# GENERADORA_V1_5.net
KiCad netlist of a schematic drawn in Altium Designer
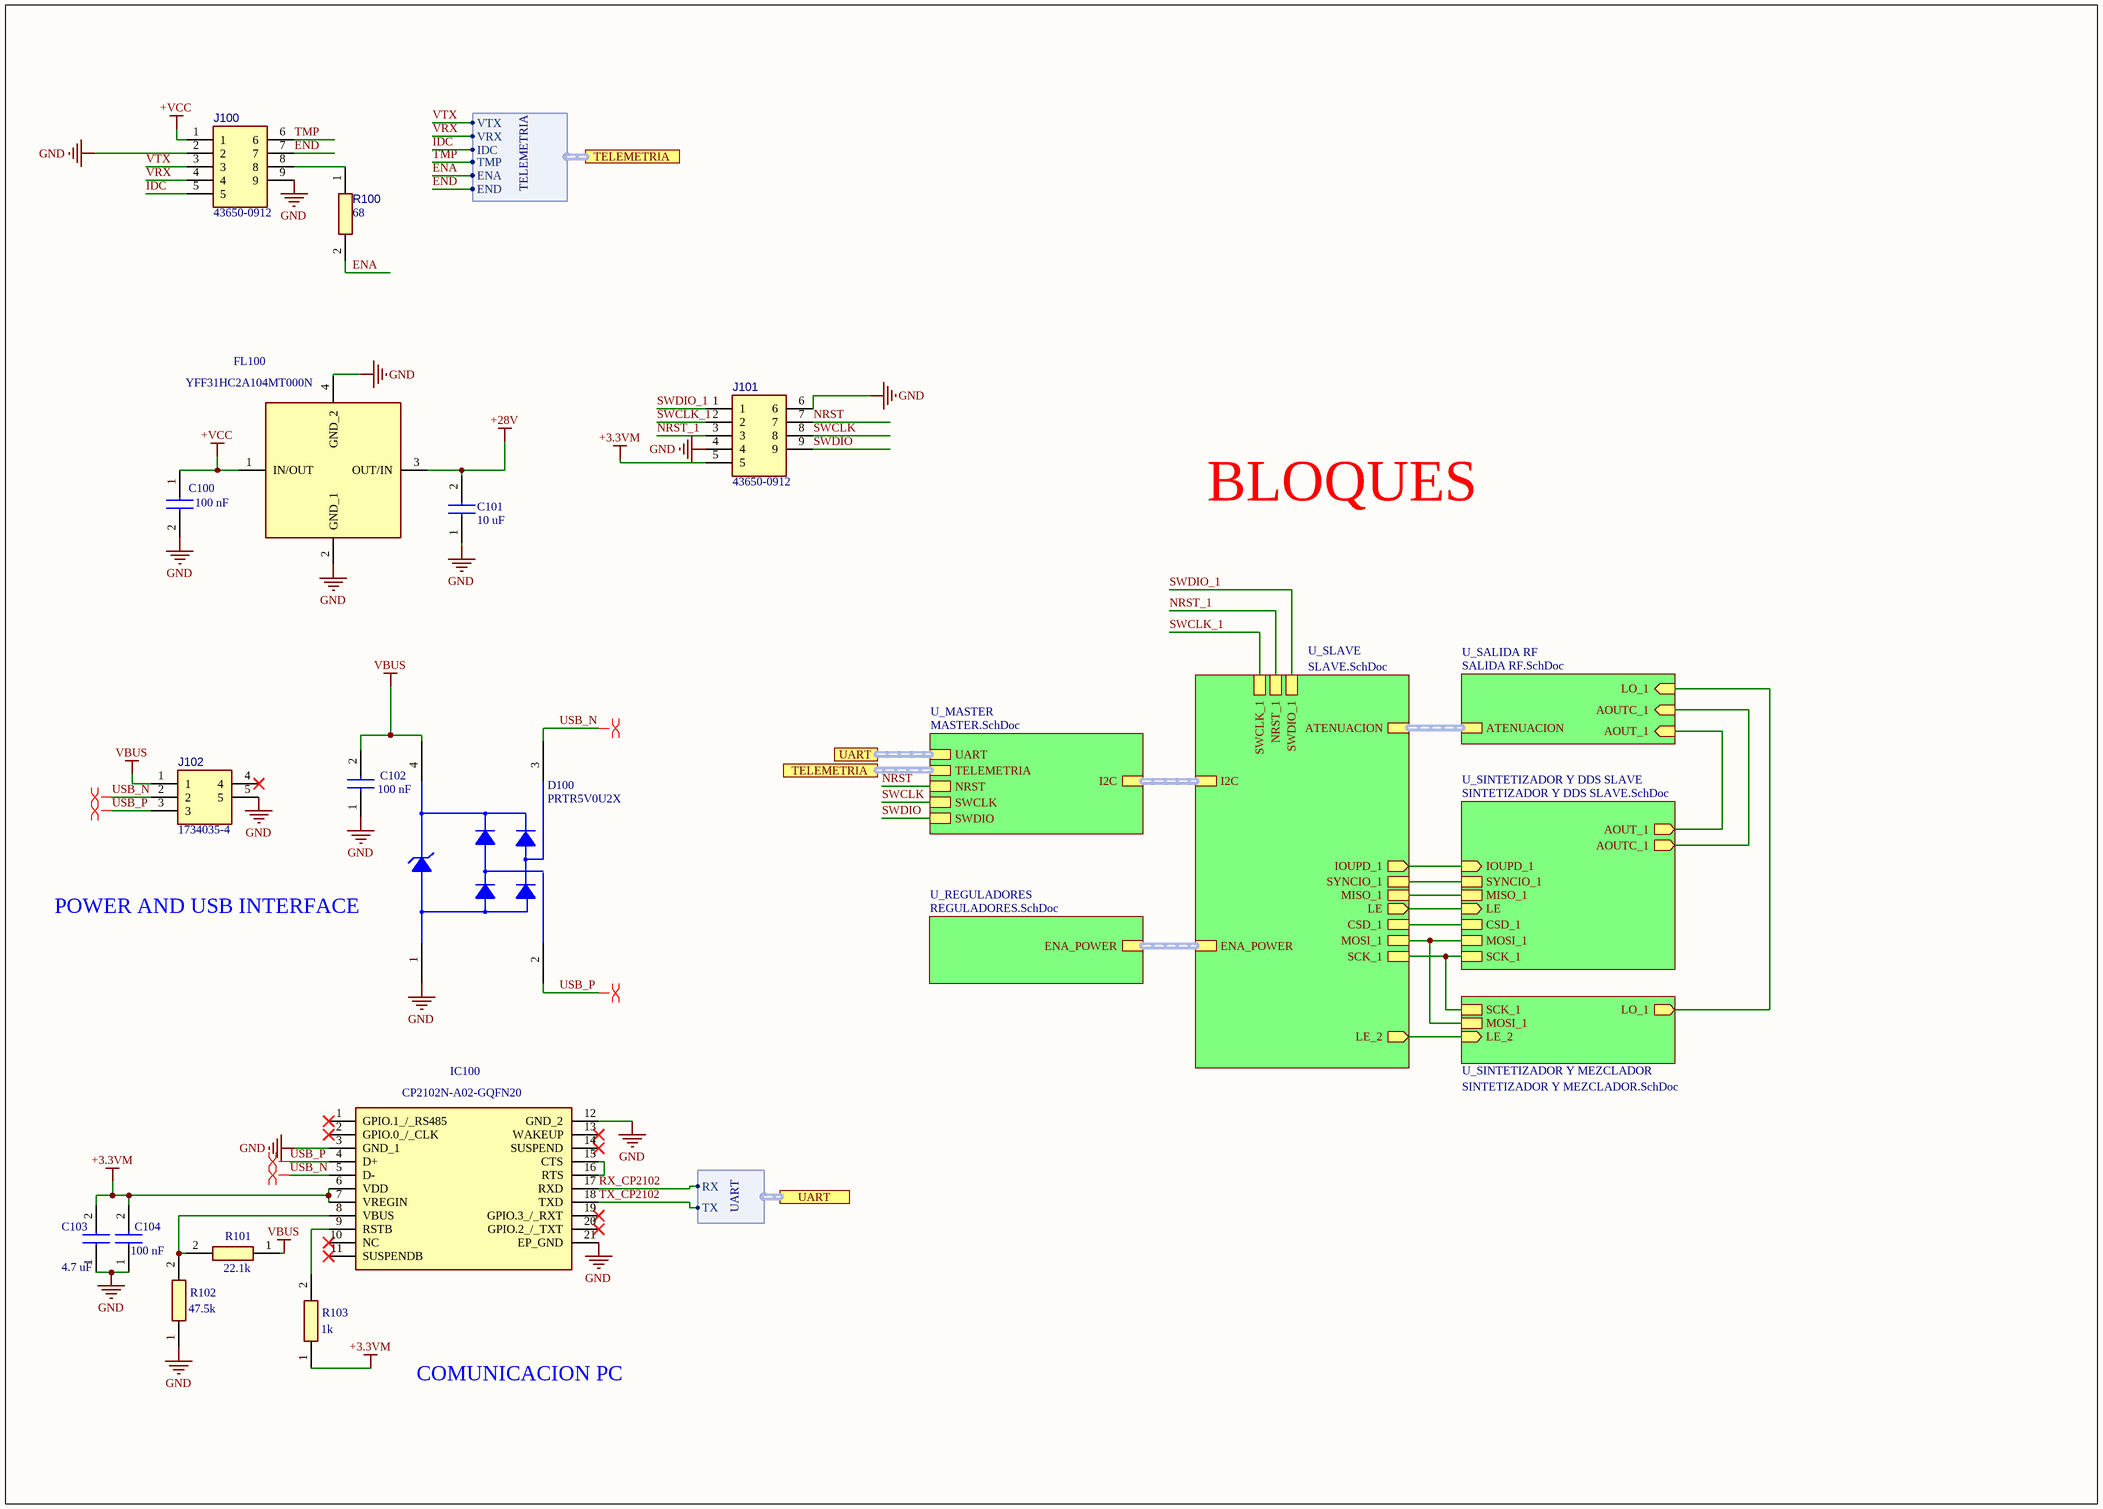
[diagram p0: GENERADORA V1.5.SchDoc]

(export (version "E")
  (design (tool "Eeschema 10.0.6"))
  (components
    (comp (ref "C100")
      (value "100 nF")
      (footprint "SamacSys:CAPC3216X94N")
      (description "Capacitor")
      (fields
        (field (name "MANUFACTURER_PART_NUMBER") "KAM31BR81H103KT")
        (field (name "MOUSER PART NUMBER") "581-KAM31BR81H103KT")
      )
      (libsource (lib "LIBRERIA_GEN_V2.0") (part "KAM31BR81H103KT"))
    )
    (comp (ref "C101")
      (value "10 uF")
      (footprint "SamacSys:CAPC3216X94N")
      (description "Capacitor")
      (fields
        (field (name "MANUFACTURER_PART_NUMBER") "KAM31BR81H103KT")
        (field (name "MOUSER PART NUMBER") "581-KAM31BR81H103KT")
      )
      (libsource (lib "LIBRERIA_GEN_V2.0") (part "KAM31BR81H103KT"))
    )
    (comp (ref "C102")
      (value "100 nF")
      (footprint "SamacSys:CAPC3216X94N")
      (description "Capacitor")
      (fields
        (field (name "MANUFACTURER_PART_NUMBER") "KAM31BR81H103KT")
        (field (name "MOUSER PART NUMBER") "581-KAM31BR81H103KT")
      )
      (libsource (lib "LIBRERIA_GEN_V2.0") (part "KAM31BR81H103KT"))
    )
    (comp (ref "C103")
      (value "4.7 uF")
      (footprint "SamacSys:C0603")
      (description "Capacitor")
      (fields (field (name "MANUFACTURER_PART_NUMBER") "C0603H470J5GACTU"))
      (libsource (lib "LIBRERIA_GEN_V2.0") (part "C0603H470J5GACTU"))
    )
    (comp (ref "C104")
      (value "100 nF")
      (footprint "SamacSys:C0603")
      (description "Capacitor")
      (fields (field (name "MANUFACTURER_PART_NUMBER") "C0603H470J5GACTU"))
      (libsource (lib "LIBRERIA_GEN_V2.0") (part "C0603H470J5GACTU"))
    )
    (comp (ref "D100")
      (value "PRTR5V0U2X")
      (footprint "AP4-00001")
      (description "Double rail-to-rail USB ESD protection diode")
      (fields (field (name "MANUFACTURER") "Philips"))
      (libsource (lib "SAM4S_Xplained_Pro") (part "PRTR5V0U2X"))
    )
    (comp (ref "FL100")
      (value "YFF31HC2A104MT000N")
      (footprint "SamacSys:YFF31HC2A104MT000N")
      (description "Filter")
      (fields (field (name "MOUSER PART NUMBER") "810-YFF31HC2A104MTHN"))
      (libsource (lib "LIBRERIA_GEN_V2.0") (part "YFF31HC2A104MT000N"))
    )
    (comp (ref "IC100")
      (value "CP2102N-A02-GQFN20")
      (footprint "SamacSys:CP2102NA02GQFN20")
      (description "Integrated Circuit")
      (fields (field (name "MOUSER PART NUMBER") "634-CP2102NA02GQFN20"))
      (libsource (lib "LIBRERIA_GEN_V2.0") (part "CP2102N-A02-GQFN20"))
    )
    (comp (ref "J100")
      (value "43650-0912")
      (footprint "SamacSys:43650-09(12,13,14)")
      (description "Connector")
      (fields (field (name "MOUSER PART NUMBER") "538-43650-0912"))
      (libsource (lib "*") (part "43650-0912"))
    )
    (comp (ref "J101")
      (value "43650-0912")
      (footprint "SamacSys:43650-09(12,13,14)")
      (description "Connector")
      (fields (field (name "MOUSER PART NUMBER") "538-43650-0912"))
      (libsource (lib "*") (part "43650-0912"))
    )
    (comp (ref "J102")
      (value "1734035-4")
      (footprint "SamacSys:1734035-2USB")
      (description "Connector")
      (fields (field (name "MOUSER PART NUMBER") "571-1734035-4"))
      (libsource (lib "SamacSys") (part "1734035-4"))
    )
    (comp (ref "R100")
      (value "68")
      (footprint "SamacSys:RESC1608X55N")
      (description "Resistor")
      (fields
        (field (name "MANUFACTURER_PART_NUMBER") "CR0603-FX-1431ELF")
        (field (name "MOUSER PART NUMBER") "652-CR0603FX-1431ELF")
      )
      (libsource (lib "*") (part "CR0603-FX-1431ELF"))
    )
    (comp (ref "R101")
      (value "22.1k")
      (footprint "SamacSys:RESC1608X55N")
      (description "Resistor")
      (fields
        (field (name "MANUFACTURER_PART_NUMBER") "CR0603-FX-1431ELF")
        (field (name "MOUSER PART NUMBER") "652-CR0603FX-1431ELF")
      )
      (libsource (lib "LIBRERIA_GEN_V2.0") (part "CR0603-FX-1431ELF"))
    )
    (comp (ref "R102")
      (value "47.5k")
      (footprint "SamacSys:RESC1608X55N")
      (description "Resistor")
      (fields
        (field (name "MANUFACTURER_PART_NUMBER") "CR0603-FX-1431ELF")
        (field (name "MOUSER PART NUMBER") "652-CR0603FX-1431ELF")
      )
      (libsource (lib "") (part "CR0603-FX-1431ELF_1"))
    )
    (comp (ref "R103")
      (value "1k")
      (footprint "SamacSys:RESC1608X55N")
      (description "Resistor")
      (fields
        (field (name "MANUFACTURER_PART_NUMBER") "CR0603-FX-1431ELF")
        (field (name "MOUSER PART NUMBER") "652-CR0603FX-1431ELF")
      )
      (libsource (lib "") (part "CR0603-FX-1431ELF_1"))
    )
  )
  (nets
    (net (code "4") (name "+3.3VM") (class "Default")
      (node (ref "C103") (pin "2") (pinfunction "2_2") (pintype "passive"))
      (node (ref "C104") (pin "2") (pinfunction "2_2") (pintype "passive"))
      (node (ref "IC100") (pin "6") (pinfunction "VDD_6") (pintype "passive"))
      (node (ref "IC100") (pin "7") (pinfunction "VREGIN_7") (pintype "passive"))
      (node (ref "J101") (pin "5") (pinfunction "5_5") (pintype "passive"))
      (node (ref "R103") (pin "1") (pinfunction "1_1") (pintype "passive"))
    )
    (net (code "5") (name "+28V") (class "Default")
      (node (ref "C101") (pin "2") (pinfunction "2_2") (pintype "passive"))
      (node (ref "FL100") (pin "3") (pinfunction "OUT/IN_3") (pintype "passive"))
    )
    (net (code "6") (name "+VCC") (class "Default")
      (node (ref "C100") (pin "1") (pinfunction "1_1") (pintype "passive"))
      (node (ref "FL100") (pin "1") (pinfunction "IN/OUT_1") (pintype "passive"))
      (node (ref "J100") (pin "1") (pinfunction "1_1") (pintype "passive"))
    )
    (net (code "11") (name "/ENA") (class "Default")
      (node (ref "R100") (pin "2") (pinfunction "2_2") (pintype "passive"))
    )
    (net (code "13") (name "/END") (class "Default")
      (node (ref "J100") (pin "7") (pinfunction "7_7") (pintype "passive"))
    )
    (net (code "15") (name "/IDC") (class "Default")
      (node (ref "J100") (pin "5") (pinfunction "5_5") (pintype "passive"))
    )
    (net (code "22") (name "/NRST") (class "Default")
      (node (ref "J101") (pin "7") (pinfunction "7_7") (pintype "passive"))
    )
    (net (code "23") (name "/NRST_1") (class "Default")
      (node (ref "J101") (pin "3") (pinfunction "3_3") (pintype "passive"))
    )
    (net (code "24") (name "/RX_CP2102") (class "Default")
      (node (ref "IC100") (pin "17") (pinfunction "RXD_17") (pintype "passive"))
    )
    (net (code "26") (name "/SWCLK") (class "Default")
      (node (ref "J101") (pin "8") (pinfunction "8_8") (pintype "passive"))
    )
    (net (code "27") (name "/SWCLK_1") (class "Default")
      (node (ref "J101") (pin "2") (pinfunction "2_2") (pintype "passive"))
    )
    (net (code "28") (name "/SWDIO") (class "Default")
      (node (ref "J101") (pin "9") (pinfunction "9_9") (pintype "passive"))
    )
    (net (code "29") (name "/SWDIO_1") (class "Default")
      (node (ref "J101") (pin "1") (pinfunction "1_1") (pintype "passive"))
    )
    (net (code "31") (name "/TMP") (class "Default")
      (node (ref "J100") (pin "6") (pinfunction "6_6") (pintype "passive"))
    )
    (net (code "32") (name "/TX_CP2102") (class "Default")
      (node (ref "IC100") (pin "18") (pinfunction "TXD_18") (pintype "passive"))
    )
    (net (code "34") (name "/USB_N") (class "Default")
      (node (ref "D100") (pin "3") (pinfunction "I/O_2_3") (pintype "passive"))
      (node (ref "IC100") (pin "5") (pinfunction "D-_5") (pintype "passive"))
      (node (ref "J102") (pin "2") (pinfunction "2_2") (pintype "passive"))
    )
    (net (code "35") (name "/USB_P") (class "Default")
      (node (ref "D100") (pin "2") (pinfunction "I/O_1_2") (pintype "passive"))
      (node (ref "IC100") (pin "4") (pinfunction "D+_4") (pintype "passive"))
      (node (ref "J102") (pin "3") (pinfunction "3_3") (pintype "passive"))
    )
    (net (code "36") (name "/VRX") (class "Default")
      (node (ref "J100") (pin "4") (pinfunction "4_4") (pintype "passive"))
    )
    (net (code "37") (name "/VTX") (class "Default")
      (node (ref "J100") (pin "3") (pinfunction "3_3") (pintype "passive"))
    )
    (net (code "40") (name "GND") (class "Default")
      (node (ref "C100") (pin "2") (pinfunction "2_2") (pintype "passive"))
      (node (ref "C101") (pin "1") (pinfunction "1_1") (pintype "passive"))
      (node (ref "C102") (pin "1") (pinfunction "1_1") (pintype "passive"))
      (node (ref "C103") (pin "1") (pinfunction "1_1") (pintype "passive"))
      (node (ref "C104") (pin "1") (pinfunction "1_1") (pintype "passive"))
      (node (ref "D100") (pin "1") (pinfunction "GND_1") (pintype "passive"))
      (node (ref "FL100") (pin "2") (pinfunction "GND_1_2") (pintype "passive"))
      (node (ref "FL100") (pin "4") (pinfunction "GND_2_4") (pintype "passive"))
      (node (ref "IC100") (pin "12") (pinfunction "GND_2_12") (pintype "passive"))
      (node (ref "IC100") (pin "21") (pinfunction "EP_GND_21") (pintype "passive"))
      (node (ref "IC100") (pin "3") (pinfunction "GND_1_3") (pintype "passive"))
      (node (ref "J100") (pin "2") (pinfunction "2_2") (pintype "passive"))
      (node (ref "J100") (pin "9") (pinfunction "9_9") (pintype "passive"))
      (node (ref "J101") (pin "4") (pinfunction "4_4") (pintype "passive"))
      (node (ref "J101") (pin "6") (pinfunction "6_6") (pintype "passive"))
      (node (ref "J102") (pin "5") (pinfunction "5_5") (pintype "passive"))
      (node (ref "R102") (pin "1") (pinfunction "1_1") (pintype "passive"))
    )
    (net (code "41") (name "Net-(IC100-CTS)") (class "Default")
      (node (ref "IC100") (pin "15") (pinfunction "CTS_15") (pintype "passive"))
      (node (ref "IC100") (pin "16") (pinfunction "RTS_16") (pintype "passive"))
    )
    (net (code "42") (name "Net-(IC100-RSTB)") (class "Default")
      (node (ref "IC100") (pin "9") (pinfunction "RSTB_9") (pintype "passive"))
      (node (ref "R103") (pin "2") (pinfunction "2_2") (pintype "passive"))
    )
    (net (code "43") (name "Net-(IC100-VBUS)") (class "Default")
      (node (ref "IC100") (pin "8") (pinfunction "VBUS_8") (pintype "passive"))
      (node (ref "R101") (pin "2") (pinfunction "2_2") (pintype "passive"))
      (node (ref "R102") (pin "2") (pinfunction "2_2") (pintype "passive"))
    )
    (net (code "44") (name "Net-(J100-Pad8)") (class "Default")
      (node (ref "J100") (pin "8") (pinfunction "8_8") (pintype "passive"))
      (node (ref "R100") (pin "1") (pinfunction "1_1") (pintype "passive"))
    )
    (net (code "45") (name "VBUS") (class "Default")
      (node (ref "C102") (pin "2") (pinfunction "2_2") (pintype "passive"))
      (node (ref "D100") (pin "4") (pinfunction "VCC_4") (pintype "passive"))
      (node (ref "J102") (pin "1") (pinfunction "1_1") (pintype "passive"))
      (node (ref "R101") (pin "1") (pinfunction "1_1") (pintype "passive"))
    )
    (net (code "46") (name "unconnected-(IC100-GPIO.0_{slash}_CLK-Pad2)") (class "Default")
      (node (ref "IC100") (pin "2") (pinfunction "GPIO.0_/_CLK_2") (pintype "passive+no_connect"))
    )
    (net (code "47") (name "unconnected-(IC100-GPIO.1_{slash}_RS485-Pad1)") (class "Default")
      (node (ref "IC100") (pin "1") (pinfunction "GPIO.1_/_RS485_1") (pintype "passive+no_connect"))
    )
    (net (code "48") (name "unconnected-(IC100-GPIO.2_{slash}_TXT-Pad20)") (class "Default")
      (node (ref "IC100") (pin "20") (pinfunction "GPIO.2_/_TXT_20") (pintype "passive+no_connect"))
    )
    (net (code "49") (name "unconnected-(IC100-GPIO.3_{slash}_RXT-Pad19)") (class "Default")
      (node (ref "IC100") (pin "19") (pinfunction "GPIO.3_/_RXT_19") (pintype "passive+no_connect"))
    )
    (net (code "50") (name "unconnected-(IC100-NC-Pad10)") (class "Default")
      (node (ref "IC100") (pin "10") (pinfunction "NC_10") (pintype "passive+no_connect"))
    )
    (net (code "51") (name "unconnected-(IC100-SUSPEND-Pad14)") (class "Default")
      (node (ref "IC100") (pin "14") (pinfunction "SUSPEND_14") (pintype "passive+no_connect"))
    )
    (net (code "52") (name "unconnected-(IC100-SUSPENDB-Pad11)") (class "Default")
      (node (ref "IC100") (pin "11") (pinfunction "SUSPENDB_11") (pintype "passive+no_connect"))
    )
    (net (code "53") (name "unconnected-(IC100-WAKEUP-Pad13)") (class "Default")
      (node (ref "IC100") (pin "13") (pinfunction "WAKEUP_13") (pintype "passive+no_connect"))
    )
    (net (code "54") (name "unconnected-(J102-Pad4)") (class "Default")
      (node (ref "J102") (pin "4") (pinfunction "4_4") (pintype "passive+no_connect"))
    )
  )
)
